# Grove_-_LoRa_Radio_868MHz_v1_0.net
KiCad netlist of a schematic drawn in EAGLE
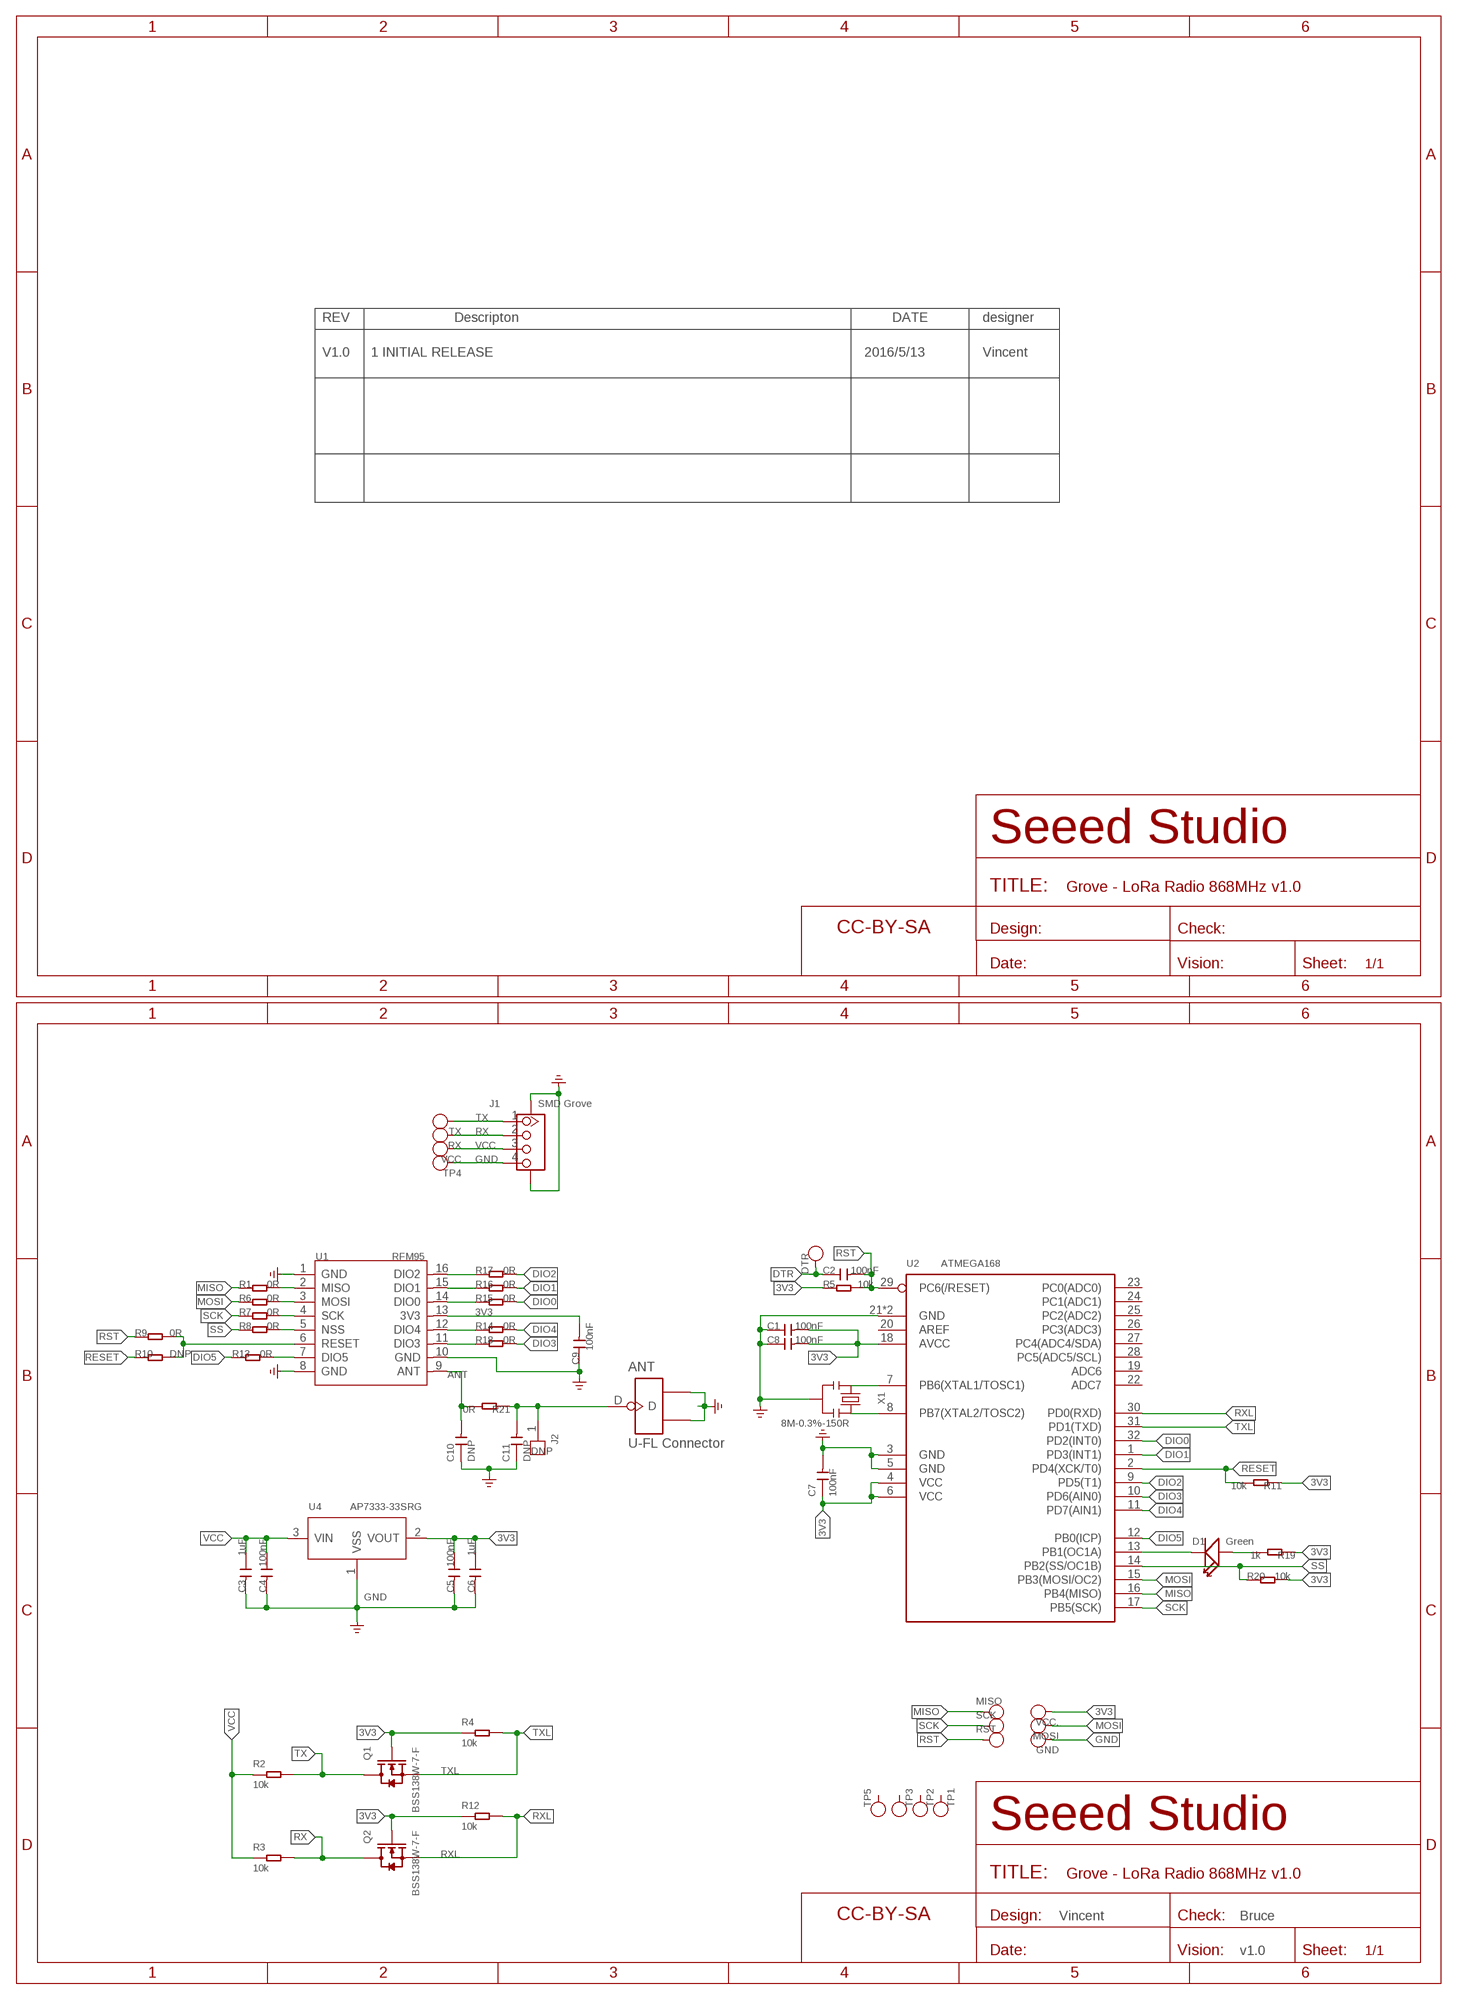
[diagram p0: schematic, sheet 1]

(export (version "E")
  (design (tool "Eeschema 10.0.6"))
  (components
    (comp (ref "ANT")
      (value "U-FL Connector")
      (footprint "eagle-import:U-FL3P-SMD-2.6X2.6X1.0MM")
      (libsource (lib "eagle-import") (part "ANTENNA-U-FL"))
    )
    (comp (ref "C1")
      (value "100nF")
      (footprint "eagle-import:C0402")
      (libsource (lib "eagle-import") (part "CAP-0402"))
    )
    (comp (ref "C2")
      (value "100nF")
      (footprint "eagle-import:C0402")
      (libsource (lib "eagle-import") (part "CAP-0402"))
    )
    (comp (ref "C3")
      (value "1uF")
      (footprint "eagle-import:C0402")
      (libsource (lib "eagle-import") (part "CAP-0402"))
    )
    (comp (ref "C4")
      (value "100nF")
      (footprint "eagle-import:C0402")
      (libsource (lib "eagle-import") (part "CAP-0402"))
    )
    (comp (ref "C5")
      (value "100nF")
      (footprint "eagle-import:C0402")
      (libsource (lib "eagle-import") (part "CAP-0402"))
    )
    (comp (ref "C6")
      (value "1uF")
      (footprint "eagle-import:C0402")
      (libsource (lib "eagle-import") (part "CAP-0402"))
    )
    (comp (ref "C7")
      (value "100nF")
      (footprint "eagle-import:C0402")
      (libsource (lib "eagle-import") (part "CAP-0402"))
    )
    (comp (ref "C8")
      (value "100nF")
      (footprint "eagle-import:C0402")
      (libsource (lib "eagle-import") (part "CAP-0402"))
    )
    (comp (ref "C9")
      (value "100nF")
      (footprint "eagle-import:C0402")
      (libsource (lib "eagle-import") (part "CAP-0402"))
    )
    (comp (ref "C10")
      (value "DNP")
      (footprint "eagle-import:C0402")
      (libsource (lib "eagle-import") (part "CAP-0402"))
    )
    (comp (ref "C11")
      (value "DNP")
      (footprint "eagle-import:C0402")
      (libsource (lib "eagle-import") (part "CAP-0402"))
    )
    (comp (ref "D1")
      (value "Green")
      (footprint "eagle-import:LED-0402")
      (libsource (lib "eagle-import") (part "LED-0402"))
    )
    (comp (ref "DTR")
      (value "TEST-POINT'4545'")
      (footprint "eagle-import:TP-D45MIL")
      (fields (field (name "PARTNO") "DNP"))
      (libsource (lib "eagle-import") (part "TEST-POINT'4545'"))
    )
    (comp (ref "FR1")
      (value "SEEEDSTUDIO-OPEN-SCH-FRAME")
      (footprint "eagle-import:SEEEDSTUDIO-PCB-FRAME")
      (libsource (lib "eagle-import") (part "SEEEDSTUDIO-OPEN-SCH-FRAME"))
    )
    (comp (ref "FR2")
      (value "SEEEDSTUDIO-OPEN-SCH-FRAME")
      (footprint "eagle-import:SEEEDSTUDIO-PCB-FRAME")
      (libsource (lib "eagle-import") (part "SEEEDSTUDIO-OPEN-SCH-FRAME"))
    )
    (comp (ref "GND")
      (value "DNP")
      (footprint "eagle-import:TP-D45MIL")
      (libsource (lib "eagle-import") (part "PAD-TEST-POINT'4545'"))
    )
    (comp (ref "J1")
      (value "SMD Grove")
      (footprint "eagle-import:HW4-SMD-2.0")
      (libsource (lib "eagle-import") (part "GROVE-CONNECTOR-SMD'DD'"))
    )
    (comp (ref "J2")
      (value "DNP")
      (footprint "eagle-import:1P-65_35MIL")
      (libsource (lib "eagle-import") (part "HEADER-1P-35"))
    )
    (comp (ref "MISO")
      (value "DNP")
      (footprint "eagle-import:TP-D45MIL")
      (libsource (lib "eagle-import") (part "PAD-TEST-POINT'4545'"))
    )
    (comp (ref "MOSI")
      (value "DNP")
      (footprint "eagle-import:TP-D45MIL")
      (libsource (lib "eagle-import") (part "PAD-TEST-POINT'4545'"))
    )
    (comp (ref "Q1")
      (value "BSS138W-7-F")
      (footprint "eagle-import:SOT-323")
      (libsource (lib "eagle-import") (part "MOSFET-N'SI1304BDL'"))
    )
    (comp (ref "Q2")
      (value "BSS138W-7-F")
      (footprint "eagle-import:SOT-323")
      (libsource (lib "eagle-import") (part "MOSFET-N'SI1304BDL'"))
    )
    (comp (ref "R1")
      (value "0R")
      (footprint "eagle-import:R0402")
      (libsource (lib "eagle-import") (part "RES-0402"))
    )
    (comp (ref "R2")
      (value "10k")
      (footprint "eagle-import:R0402")
      (libsource (lib "eagle-import") (part "RES-0402"))
    )
    (comp (ref "R3")
      (value "10k")
      (footprint "eagle-import:R0402")
      (libsource (lib "eagle-import") (part "RES-0402"))
    )
    (comp (ref "R4")
      (value "10k")
      (footprint "eagle-import:R0402")
      (libsource (lib "eagle-import") (part "RES-0402"))
    )
    (comp (ref "R5")
      (value "10k")
      (footprint "eagle-import:R0402")
      (libsource (lib "eagle-import") (part "RES-0402"))
    )
    (comp (ref "R6")
      (value "0R")
      (footprint "eagle-import:R0402")
      (libsource (lib "eagle-import") (part "RES-0402"))
    )
    (comp (ref "R7")
      (value "0R")
      (footprint "eagle-import:R0402")
      (libsource (lib "eagle-import") (part "RES-0402"))
    )
    (comp (ref "R8")
      (value "0R")
      (footprint "eagle-import:R0402")
      (libsource (lib "eagle-import") (part "RES-0402"))
    )
    (comp (ref "R9")
      (value "0R")
      (footprint "eagle-import:R0402")
      (libsource (lib "eagle-import") (part "RES-0402"))
    )
    (comp (ref "R10")
      (value "DNP")
      (footprint "eagle-import:R0402")
      (libsource (lib "eagle-import") (part "RES-0402"))
    )
    (comp (ref "R11")
      (value "10k")
      (footprint "eagle-import:R0402")
      (libsource (lib "eagle-import") (part "RES-0402"))
    )
    (comp (ref "R12")
      (value "10k")
      (footprint "eagle-import:R0402")
      (libsource (lib "eagle-import") (part "RES-0402"))
    )
    (comp (ref "R13")
      (value "0R")
      (footprint "eagle-import:R0402")
      (libsource (lib "eagle-import") (part "RES-0402"))
    )
    (comp (ref "R14")
      (value "0R")
      (footprint "eagle-import:R0402")
      (libsource (lib "eagle-import") (part "RES-0402"))
    )
    (comp (ref "R15")
      (value "0R")
      (footprint "eagle-import:R0402")
      (libsource (lib "eagle-import") (part "RES-0402"))
    )
    (comp (ref "R16")
      (value "0R")
      (footprint "eagle-import:R0402")
      (libsource (lib "eagle-import") (part "RES-0402"))
    )
    (comp (ref "R17")
      (value "0R")
      (footprint "eagle-import:R0402")
      (libsource (lib "eagle-import") (part "RES-0402"))
    )
    (comp (ref "R18")
      (value "0R")
      (footprint "eagle-import:R0402")
      (libsource (lib "eagle-import") (part "RES-0402"))
    )
    (comp (ref "R19")
      (value "1k")
      (footprint "eagle-import:R0402")
      (libsource (lib "eagle-import") (part "RES-0402"))
    )
    (comp (ref "R20")
      (value "10k")
      (footprint "eagle-import:R0402")
      (libsource (lib "eagle-import") (part "RES-0402"))
    )
    (comp (ref "R21")
      (value "0R")
      (footprint "eagle-import:R0603")
      (libsource (lib "eagle-import") (part "R-0603"))
    )
    (comp (ref "RST")
      (value "DNP")
      (footprint "eagle-import:TP-D45MIL")
      (libsource (lib "eagle-import") (part "PAD-TEST-POINT'4545'"))
    )
    (comp (ref "RX")
      (value "TEST-POINT'4545'")
      (footprint "eagle-import:TP-D45MIL")
      (fields (field (name "PARTNO") "DNP"))
      (libsource (lib "eagle-import") (part "TEST-POINT'4545'"))
    )
    (comp (ref "SCK")
      (value "DNP")
      (footprint "eagle-import:TP-D45MIL")
      (libsource (lib "eagle-import") (part "PAD-TEST-POINT'4545'"))
    )
    (comp (ref "TP1")
      (value "TEST-POINT'4545'")
      (footprint "eagle-import:TP-D45MIL")
      (fields (field (name "PARTNO") "DNP"))
      (libsource (lib "eagle-import") (part "TEST-POINT'4545'"))
    )
    (comp (ref "TP2")
      (value "TEST-POINT'4545'")
      (footprint "eagle-import:TP-D45MIL")
      (fields (field (name "PARTNO") "DNP"))
      (libsource (lib "eagle-import") (part "TEST-POINT'4545'"))
    )
    (comp (ref "TP3")
      (value "TEST-POINT'4545'")
      (footprint "eagle-import:TP-D45MIL")
      (fields (field (name "PARTNO") "DNP"))
      (libsource (lib "eagle-import") (part "TEST-POINT'4545'"))
    )
    (comp (ref "TP4")
      (value "TEST-POINT'4545'")
      (footprint "eagle-import:TP-D45MIL")
      (fields (field (name "PARTNO") "DNP"))
      (libsource (lib "eagle-import") (part "TEST-POINT'4545'"))
    )
    (comp (ref "TP5")
      (value "TEST-POINT'4545'")
      (footprint "eagle-import:TP-D45MIL")
      (fields (field (name "PARTNO") "DNP"))
      (libsource (lib "eagle-import") (part "TEST-POINT'4545'"))
    )
    (comp (ref "TX")
      (value "TEST-POINT'4545'")
      (footprint "eagle-import:TP-D45MIL")
      (fields (field (name "PARTNO") "DNP"))
      (libsource (lib "eagle-import") (part "TEST-POINT'4545'"))
    )
    (comp (ref "U1")
      (value "RFM95")
      (footprint "eagle-import:MODEM16-2-16X16X1.8MM")
      (libsource (lib "eagle-import") (part "MOUDLE-MODEM-RFM95/96/97/98"))
    )
    (comp (ref "U2")
      (value "ATMEGA168")
      (footprint "eagle-import:QFN32G-0.5-5X5MM")
      (libsource (lib "eagle-import") (part "MCU-ATMEGA8/168/328MU"))
    )
    (comp (ref "U4")
      (value "AP7333-33SRG")
      (footprint "eagle-import:SOT-23")
      (libsource (lib "eagle-import") (part "PMIC-XC6206PMR"))
    )
    (comp (ref "VCC")
      (value "TEST-POINT'4545'")
      (footprint "eagle-import:TP-D45MIL")
      (fields (field (name "PARTNO") "DNP"))
      (libsource (lib "eagle-import") (part "TEST-POINT'4545'"))
    )
    (comp (ref "VCC.")
      (value "NC")
      (footprint "eagle-import:TP-D45MIL")
      (fields (field (name "PARTNO") "DNP"))
      (libsource (lib "eagle-import") (part "PAD-TEST-POINT'4545'"))
    )
    (comp (ref "X1")
      (value "8M-0.3%-150R")
      (footprint "eagle-import:RESONATOR3-SMD-3.6X1.3X0.8MM")
      (libsource (lib "eagle-import") (part "CRYSTAL-RESONATOR'SMD'"))
    )
  )
  (nets
    (net (code "1") (name "/ANT") (class "Default")
      (node (ref "C10") (pin "2") (pinfunction "2_2") (pintype "passive"))
      (node (ref "R21") (pin "2") (pinfunction "2_2") (pintype "passive"))
      (node (ref "U1") (pin "9") (pinfunction "ANT_9") (pintype "bidirectional"))
    )
    (net (code "2") (name "3V3") (class "Default")
      (node (ref "C1") (pin "2") (pinfunction "2_2") (pintype "passive"))
      (node (ref "C5") (pin "1") (pinfunction "1_1") (pintype "passive"))
      (node (ref "C6") (pin "1") (pinfunction "1_1") (pintype "passive"))
      (node (ref "C7") (pin "1") (pinfunction "1_1") (pintype "passive"))
      (node (ref "C8") (pin "2") (pinfunction "2_2") (pintype "passive"))
      (node (ref "C9") (pin "2") (pinfunction "2_2") (pintype "passive"))
      (node (ref "Q1") (pin "1") (pinfunction "G_1") (pintype "passive"))
      (node (ref "Q2") (pin "1") (pinfunction "G_1") (pintype "passive"))
      (node (ref "R11") (pin "2") (pinfunction "2_2") (pintype "passive"))
      (node (ref "R12") (pin "1") (pinfunction "1_1") (pintype "passive"))
      (node (ref "R19") (pin "2") (pinfunction "2_2") (pintype "passive"))
      (node (ref "R20") (pin "2") (pinfunction "2_2") (pintype "passive"))
      (node (ref "R4") (pin "1") (pinfunction "1_1") (pintype "passive"))
      (node (ref "R5") (pin "2") (pinfunction "2_2") (pintype "passive"))
      (node (ref "U1") (pin "13") (pinfunction "3V3_13") (pintype "bidirectional"))
      (node (ref "U2") (pin "18") (pinfunction "AVCC_18") (pintype "bidirectional"))
      (node (ref "U2") (pin "4") (pinfunction "VCC_4") (pintype "bidirectional"))
      (node (ref "U2") (pin "6") (pinfunction "VCC_6") (pintype "bidirectional"))
      (node (ref "U4") (pin "2") (pinfunction "VOUT_2") (pintype "bidirectional"))
      (node (ref "VCC.") (pin "T") (pinfunction "T_T") (pintype "bidirectional"))
    )
    (net (code "3") (name "DIO0") (class "Default")
      (node (ref "R15") (pin "2") (pinfunction "2_2") (pintype "passive"))
      (node (ref "U2") (pin "32") (pinfunction "PD2(INT0)_32") (pintype "bidirectional"))
    )
    (net (code "4") (name "DIO1") (class "Default")
      (node (ref "R16") (pin "2") (pinfunction "2_2") (pintype "passive"))
      (node (ref "U2") (pin "1") (pinfunction "PD3(INT1)_1") (pintype "bidirectional"))
    )
    (net (code "5") (name "DIO2") (class "Default")
      (node (ref "R17") (pin "2") (pinfunction "2_2") (pintype "passive"))
      (node (ref "U2") (pin "9") (pinfunction "PD5(T1)_9") (pintype "bidirectional"))
    )
    (net (code "6") (name "DIO3") (class "Default")
      (node (ref "R18") (pin "2") (pinfunction "2_2") (pintype "passive"))
      (node (ref "U2") (pin "10") (pinfunction "PD6(AIN0)_10") (pintype "bidirectional"))
    )
    (net (code "7") (name "DIO4") (class "Default")
      (node (ref "R14") (pin "2") (pinfunction "2_2") (pintype "passive"))
      (node (ref "U2") (pin "11") (pinfunction "PD7(AIN1)_11") (pintype "bidirectional"))
    )
    (net (code "8") (name "DIO5") (class "Default")
      (node (ref "R13") (pin "1") (pinfunction "1_1") (pintype "passive"))
      (node (ref "U2") (pin "12") (pinfunction "PB0(ICP)_12") (pintype "bidirectional"))
    )
    (net (code "9") (name "DTR") (class "Default")
      (node (ref "C2") (pin "1") (pinfunction "1_1") (pintype "passive"))
      (node (ref "DTR") (pin "T") (pinfunction "T_T") (pintype "bidirectional"))
    )
    (net (code "10") (name "GND") (class "Default")
      (node (ref "ANT") (pin "GND1") (pinfunction "GND1_GND1") (pintype "bidirectional"))
      (node (ref "ANT") (pin "GND2") (pinfunction "GND2_GND2") (pintype "bidirectional"))
      (node (ref "C1") (pin "1") (pinfunction "1_1") (pintype "passive"))
      (node (ref "C10") (pin "1") (pinfunction "1_1") (pintype "passive"))
      (node (ref "C11") (pin "1") (pinfunction "1_1") (pintype "passive"))
      (node (ref "C3") (pin "2") (pinfunction "2_2") (pintype "passive"))
      (node (ref "C4") (pin "2") (pinfunction "2_2") (pintype "passive"))
      (node (ref "C5") (pin "2") (pinfunction "2_2") (pintype "passive"))
      (node (ref "C6") (pin "2") (pinfunction "2_2") (pintype "passive"))
      (node (ref "C7") (pin "2") (pinfunction "2_2") (pintype "passive"))
      (node (ref "C8") (pin "1") (pinfunction "1_1") (pintype "passive"))
      (node (ref "C9") (pin "1") (pinfunction "1_1") (pintype "passive"))
      (node (ref "GND") (pin "T") (pinfunction "T_T") (pintype "bidirectional"))
      (node (ref "J1") (pin "4") (pinfunction "4_4") (pintype "bidirectional"))
      (node (ref "J1") (pin "SS1") (pinfunction "SS1_SS1") (pintype "bidirectional"))
      (node (ref "J1") (pin "SS2") (pinfunction "SS2_SS2") (pintype "bidirectional"))
      (node (ref "TP4") (pin "T") (pinfunction "T_T") (pintype "bidirectional"))
      (node (ref "U1") (pin "1") (pinfunction "GND_1") (pintype "bidirectional"))
      (node (ref "U1") (pin "10") (pinfunction "GND_10") (pintype "bidirectional"))
      (node (ref "U1") (pin "8") (pinfunction "GND_8") (pintype "bidirectional"))
      (node (ref "U2") (pin "21") (pinfunction "GND_21") (pintype "bidirectional"))
      (node (ref "U2") (pin "3") (pinfunction "GND_3") (pintype "bidirectional"))
      (node (ref "U2") (pin "33") (pinfunction "GND_33") (pintype "bidirectional"))
      (node (ref "U2") (pin "5") (pinfunction "GND_5") (pintype "bidirectional"))
      (node (ref "U4") (pin "1") (pinfunction "VSS_1") (pintype "bidirectional"))
      (node (ref "X1") (pin "2") (pinfunction "2_2") (pintype "passive"))
    )
    (net (code "11") (name "MISO") (class "Default")
      (node (ref "MISO") (pin "T") (pinfunction "T_T") (pintype "bidirectional"))
      (node (ref "R1") (pin "1") (pinfunction "1_1") (pintype "passive"))
      (node (ref "U2") (pin "16") (pinfunction "PB4(MISO)_16") (pintype "bidirectional"))
    )
    (net (code "12") (name "MOSI") (class "Default")
      (node (ref "MOSI") (pin "T") (pinfunction "T_T") (pintype "bidirectional"))
      (node (ref "R6") (pin "1") (pinfunction "1_1") (pintype "passive"))
      (node (ref "U2") (pin "15") (pinfunction "PB3(MOSI/OC2)_15") (pintype "bidirectional"))
    )
    (net (code "13") (name "Net-(ANT-PadD)") (class "Default")
      (node (ref "ANT") (pin "D") (pinfunction "D_D") (pintype "bidirectional"))
      (node (ref "C11") (pin "2") (pinfunction "2_2") (pintype "passive"))
      (node (ref "J2") (pin "1") (pinfunction "1_1") (pintype "bidirectional"))
      (node (ref "R21") (pin "1") (pinfunction "1_1") (pintype "passive"))
    )
    (net (code "14") (name "Net-(D1-Pad+)") (class "Default")
      (node (ref "D1") (pin "+") (pinfunction "+_+") (pintype "passive"))
      (node (ref "R19") (pin "1") (pinfunction "1_1") (pintype "passive"))
    )
    (net (code "15") (name "Net-(U1-DIO0)") (class "Default")
      (node (ref "R15") (pin "1") (pinfunction "1_1") (pintype "passive"))
      (node (ref "U1") (pin "14") (pinfunction "DIO0_14") (pintype "bidirectional"))
    )
    (net (code "16") (name "Net-(U1-DIO1)") (class "Default")
      (node (ref "R16") (pin "1") (pinfunction "1_1") (pintype "passive"))
      (node (ref "U1") (pin "15") (pinfunction "DIO1_15") (pintype "bidirectional"))
    )
    (net (code "17") (name "Net-(U1-DIO2)") (class "Default")
      (node (ref "R17") (pin "1") (pinfunction "1_1") (pintype "passive"))
      (node (ref "U1") (pin "16") (pinfunction "DIO2_16") (pintype "bidirectional"))
    )
    (net (code "18") (name "Net-(U1-DIO3)") (class "Default")
      (node (ref "R18") (pin "1") (pinfunction "1_1") (pintype "passive"))
      (node (ref "U1") (pin "11") (pinfunction "DIO3_11") (pintype "bidirectional"))
    )
    (net (code "19") (name "Net-(U1-DIO4)") (class "Default")
      (node (ref "R14") (pin "1") (pinfunction "1_1") (pintype "passive"))
      (node (ref "U1") (pin "12") (pinfunction "DIO4_12") (pintype "bidirectional"))
    )
    (net (code "20") (name "Net-(U1-DIO5)") (class "Default")
      (node (ref "R13") (pin "2") (pinfunction "2_2") (pintype "passive"))
      (node (ref "U1") (pin "7") (pinfunction "DIO5_7") (pintype "bidirectional"))
    )
    (net (code "21") (name "Net-(U1-MISO)") (class "Default")
      (node (ref "R1") (pin "2") (pinfunction "2_2") (pintype "passive"))
      (node (ref "U1") (pin "2") (pinfunction "MISO_2") (pintype "bidirectional"))
    )
    (net (code "22") (name "Net-(U1-MOSI)") (class "Default")
      (node (ref "R6") (pin "2") (pinfunction "2_2") (pintype "passive"))
      (node (ref "U1") (pin "3") (pinfunction "MOSI_3") (pintype "bidirectional"))
    )
    (net (code "23") (name "Net-(U1-NSS)") (class "Default")
      (node (ref "R8") (pin "2") (pinfunction "2_2") (pintype "passive"))
      (node (ref "U1") (pin "5") (pinfunction "NSS_5") (pintype "bidirectional"))
    )
    (net (code "24") (name "Net-(U1-RESET)") (class "Default")
      (node (ref "R10") (pin "1") (pinfunction "1_1") (pintype "passive"))
      (node (ref "R9") (pin "1") (pinfunction "1_1") (pintype "passive"))
      (node (ref "U1") (pin "6") (pinfunction "RESET_6") (pintype "bidirectional"))
    )
    (net (code "25") (name "Net-(U1-SCK)") (class "Default")
      (node (ref "R7") (pin "2") (pinfunction "2_2") (pintype "passive"))
      (node (ref "U1") (pin "4") (pinfunction "SCK_4") (pintype "bidirectional"))
    )
    (net (code "26") (name "Net-(U2-PB1(OC1A))") (class "Default")
      (node (ref "D1") (pin "-") (pinfunction "-_-") (pintype "passive"))
      (node (ref "U2") (pin "13") (pinfunction "PB1(OC1A)_13") (pintype "bidirectional"))
    )
    (net (code "27") (name "Net-(U2-PB6(XTAL1{slash}TOSC1))") (class "Default")
      (node (ref "U2") (pin "7") (pinfunction "PB6(XTAL1/TOSC1)_7") (pintype "bidirectional"))
      (node (ref "X1") (pin "1") (pinfunction "1_1") (pintype "passive"))
    )
    (net (code "28") (name "Net-(U2-PB7(XTAL2{slash}TOSC2))") (class "Default")
      (node (ref "U2") (pin "8") (pinfunction "PB7(XTAL2/TOSC2)_8") (pintype "bidirectional"))
      (node (ref "X1") (pin "3") (pinfunction "3_3") (pintype "passive"))
    )
    (net (code "29") (name "RESET") (class "Default")
      (node (ref "R10") (pin "2") (pinfunction "2_2") (pintype "passive"))
      (node (ref "R11") (pin "1") (pinfunction "1_1") (pintype "passive"))
      (node (ref "U2") (pin "2") (pinfunction "PD4(XCK/T0)_2") (pintype "bidirectional"))
    )
    (net (code "30") (name "RST") (class "Default")
      (node (ref "C2") (pin "2") (pinfunction "2_2") (pintype "passive"))
      (node (ref "R5") (pin "1") (pinfunction "1_1") (pintype "passive"))
      (node (ref "R9") (pin "2") (pinfunction "2_2") (pintype "passive"))
      (node (ref "RST") (pin "T") (pinfunction "T_T") (pintype "bidirectional"))
      (node (ref "U2") (pin "29") (pinfunction "PC6(/RESET)_29") (pintype "bidirectional"))
    )
    (net (code "31") (name "RX") (class "Default")
      (node (ref "J1") (pin "2") (pinfunction "2_2") (pintype "bidirectional"))
      (node (ref "Q2") (pin "3") (pinfunction "D_3") (pintype "passive"))
      (node (ref "R3") (pin "2") (pinfunction "2_2") (pintype "passive"))
      (node (ref "RX") (pin "T") (pinfunction "T_T") (pintype "bidirectional"))
    )
    (net (code "32") (name "RXL") (class "Default")
      (node (ref "Q2") (pin "2") (pinfunction "S_2") (pintype "passive"))
      (node (ref "R12") (pin "2") (pinfunction "2_2") (pintype "passive"))
      (node (ref "U2") (pin "30") (pinfunction "PD0(RXD)_30") (pintype "bidirectional"))
    )
    (net (code "33") (name "SCK") (class "Default")
      (node (ref "R7") (pin "1") (pinfunction "1_1") (pintype "passive"))
      (node (ref "SCK") (pin "T") (pinfunction "T_T") (pintype "bidirectional"))
      (node (ref "U2") (pin "17") (pinfunction "PB5(SCK)_17") (pintype "bidirectional"))
    )
    (net (code "34") (name "SS") (class "Default")
      (node (ref "R20") (pin "1") (pinfunction "1_1") (pintype "passive"))
      (node (ref "R8") (pin "1") (pinfunction "1_1") (pintype "passive"))
      (node (ref "U2") (pin "14") (pinfunction "PB2(SS/OC1B)_14") (pintype "bidirectional"))
    )
    (net (code "35") (name "TX") (class "Default")
      (node (ref "J1") (pin "1") (pinfunction "1_1") (pintype "bidirectional"))
      (node (ref "Q1") (pin "3") (pinfunction "D_3") (pintype "passive"))
      (node (ref "R2") (pin "2") (pinfunction "2_2") (pintype "passive"))
      (node (ref "TX") (pin "T") (pinfunction "T_T") (pintype "bidirectional"))
    )
    (net (code "36") (name "TXL") (class "Default")
      (node (ref "Q1") (pin "2") (pinfunction "S_2") (pintype "passive"))
      (node (ref "R4") (pin "2") (pinfunction "2_2") (pintype "passive"))
      (node (ref "U2") (pin "31") (pinfunction "PD1(TXD)_31") (pintype "bidirectional"))
    )
    (net (code "37") (name "VCC") (class "Default")
      (node (ref "C3") (pin "1") (pinfunction "1_1") (pintype "passive"))
      (node (ref "C4") (pin "1") (pinfunction "1_1") (pintype "passive"))
      (node (ref "J1") (pin "3") (pinfunction "3_3") (pintype "bidirectional"))
      (node (ref "R2") (pin "1") (pinfunction "1_1") (pintype "passive"))
      (node (ref "R3") (pin "1") (pinfunction "1_1") (pintype "passive"))
      (node (ref "U4") (pin "3") (pinfunction "VIN_3") (pintype "bidirectional"))
      (node (ref "VCC") (pin "T") (pinfunction "T_T") (pintype "bidirectional"))
    )
    (net (code "38") (name "unconnected-(TP1-PadT)") (class "Default")
      (node (ref "TP1") (pin "T") (pinfunction "T_T") (pintype "bidirectional"))
    )
    (net (code "39") (name "unconnected-(TP2-PadT)") (class "Default")
      (node (ref "TP2") (pin "T") (pinfunction "T_T") (pintype "bidirectional"))
    )
    (net (code "40") (name "unconnected-(TP3-PadT)") (class "Default")
      (node (ref "TP3") (pin "T") (pinfunction "T_T") (pintype "bidirectional"))
    )
    (net (code "41") (name "unconnected-(TP5-PadT)") (class "Default")
      (node (ref "TP5") (pin "T") (pinfunction "T_T") (pintype "bidirectional"))
    )
    (net (code "42") (name "unconnected-(U2-ADC6-Pad19)") (class "Default")
      (node (ref "U2") (pin "19") (pinfunction "ADC6_19") (pintype "bidirectional"))
    )
    (net (code "43") (name "unconnected-(U2-ADC7-Pad22)") (class "Default")
      (node (ref "U2") (pin "22") (pinfunction "ADC7_22") (pintype "bidirectional"))
    )
    (net (code "44") (name "unconnected-(U2-AREF-Pad20)") (class "Default")
      (node (ref "U2") (pin "20") (pinfunction "AREF_20") (pintype "bidirectional"))
    )
    (net (code "45") (name "unconnected-(U2-PC0(ADC0)-Pad23)") (class "Default")
      (node (ref "U2") (pin "23") (pinfunction "PC0(ADC0)_23") (pintype "bidirectional"))
    )
    (net (code "46") (name "unconnected-(U2-PC1(ADC1)-Pad24)") (class "Default")
      (node (ref "U2") (pin "24") (pinfunction "PC1(ADC1)_24") (pintype "bidirectional"))
    )
    (net (code "47") (name "unconnected-(U2-PC2(ADC2)-Pad25)") (class "Default")
      (node (ref "U2") (pin "25") (pinfunction "PC2(ADC2)_25") (pintype "bidirectional"))
    )
    (net (code "48") (name "unconnected-(U2-PC3(ADC3)-Pad26)") (class "Default")
      (node (ref "U2") (pin "26") (pinfunction "PC3(ADC3)_26") (pintype "bidirectional"))
    )
    (net (code "49") (name "unconnected-(U2-PC4(ADC4{slash}SDA)-Pad27)") (class "Default")
      (node (ref "U2") (pin "27") (pinfunction "PC4(ADC4/SDA)_27") (pintype "bidirectional"))
    )
    (net (code "50") (name "unconnected-(U2-PC5(ADC5{slash}SCL)-Pad28)") (class "Default")
      (node (ref "U2") (pin "28") (pinfunction "PC5(ADC5/SCL)_28") (pintype "bidirectional"))
    )
  )
)
